# 5_-OPI_MAIN.net
KiCad netlist of a schematic drawn in Altium Designer
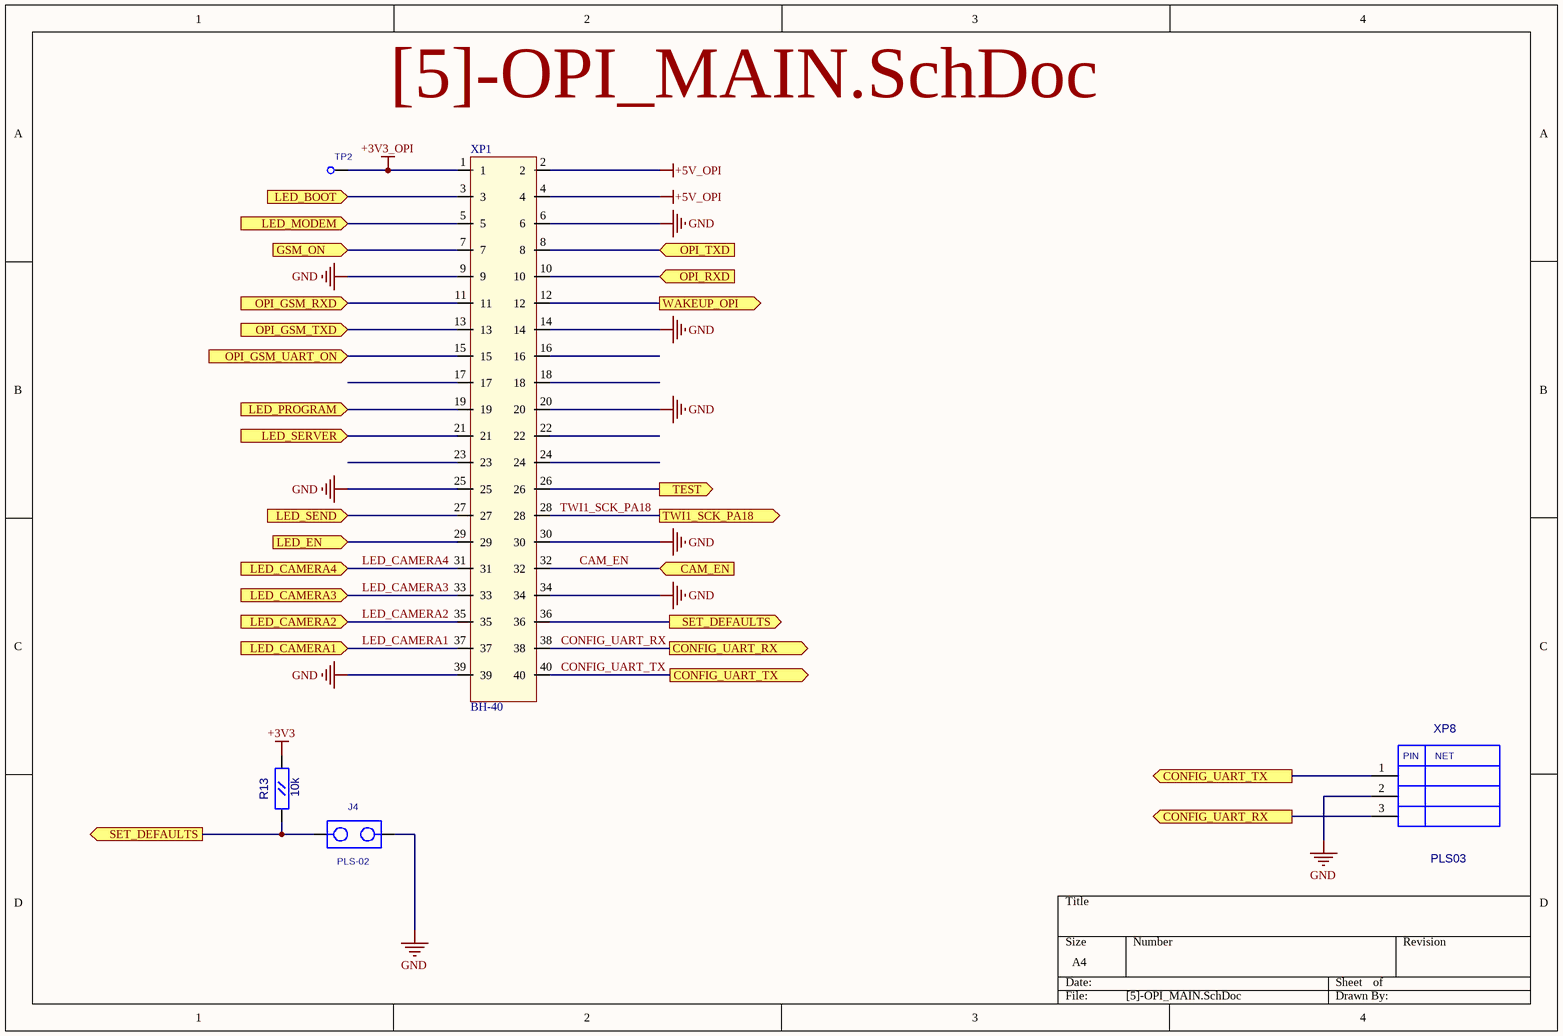
[diagram p0: [5]-OPI_MAIN.SchDoc]

(export (version "E")
  (design (tool "Eeschema 10.0.6"))
  (components
    (comp (ref "J4") (value "PLS-02") (footprint "PLS-02") (libsource (lib "fizik_lib") (part "PLS-02")))
    (comp (ref "R13")
      (value "10k")
      (footprint "RC0603")
      (description "RC0603")
      (libsource (lib "fizik_lib") (part "RC0603"))
    )
    (comp (ref "TP2")
      (value "TESTPOINT1")
      (footprint "TESTPOINT1")
      (libsource (lib "fizik_lib") (part "TESTPOINT1"))
    )
    (comp (ref "XP1")
      (value "BH-40")
      (footprint "BH-40")
      (description "2.54mm connector with key")
      (libsource (lib "fizik_lib") (part "BH-40"))
    )
    (comp (ref "XP8") (value "PLS03") (footprint "PLS-03") (libsource (lib "fizik_lib") (part "PLS03")))
  )
  (nets
    (net (code "1") (name "+3V3") (class "Default")
      (node (ref "R13") (pin "2") (pinfunction "B_2") (pintype "passive"))
    )
    (net (code "2") (name "+3V3_OPI") (class "Default")
      (node (ref "TP2") (pin "1") (pintype "passive"))
      (node (ref "XP1") (pin "1") (pinfunction "1_1") (pintype "passive"))
    )
    (net (code "3") (name "+5V_OPI") (class "Default")
      (node (ref "XP1") (pin "2") (pinfunction "2_2") (pintype "passive"))
      (node (ref "XP1") (pin "4") (pinfunction "4_4") (pintype "passive"))
    )
    (net (code "4") (name "/CAM_EN") (class "Default")
      (node (ref "XP1") (pin "32") (pinfunction "32_32") (pintype "passive"))
    )
    (net (code "5") (name "/CONFIG_UART_RX") (class "Default")
      (node (ref "XP1") (pin "38") (pinfunction "38_38") (pintype "passive"))
      (node (ref "XP8") (pin "3") (pinfunction "3_3") (pintype "passive"))
    )
    (net (code "6") (name "/CONFIG_UART_TX") (class "Default")
      (node (ref "XP1") (pin "40") (pinfunction "40_40") (pintype "passive"))
      (node (ref "XP8") (pin "1") (pinfunction "1_1") (pintype "passive"))
    )
    (net (code "7") (name "/GSM_ON") (class "Default")
      (node (ref "XP1") (pin "7") (pinfunction "7_7") (pintype "passive"))
    )
    (net (code "8") (name "/LED_BOOT") (class "Default")
      (node (ref "XP1") (pin "3") (pinfunction "3_3") (pintype "passive"))
    )
    (net (code "9") (name "/LED_CAMERA1") (class "Default")
      (node (ref "XP1") (pin "37") (pinfunction "37_37") (pintype "passive"))
    )
    (net (code "10") (name "/LED_CAMERA2") (class "Default")
      (node (ref "XP1") (pin "35") (pinfunction "35_35") (pintype "passive"))
    )
    (net (code "11") (name "/LED_CAMERA3") (class "Default")
      (node (ref "XP1") (pin "33") (pinfunction "33_33") (pintype "passive"))
    )
    (net (code "12") (name "/LED_CAMERA4") (class "Default")
      (node (ref "XP1") (pin "31") (pinfunction "31_31") (pintype "passive"))
    )
    (net (code "13") (name "/LED_EN") (class "Default")
      (node (ref "XP1") (pin "29") (pinfunction "29_29") (pintype "passive"))
    )
    (net (code "14") (name "/LED_MODEM") (class "Default")
      (node (ref "XP1") (pin "5") (pinfunction "5_5") (pintype "passive"))
    )
    (net (code "15") (name "/LED_PROGRAM") (class "Default")
      (node (ref "XP1") (pin "19") (pinfunction "19_19") (pintype "passive"))
    )
    (net (code "16") (name "/LED_SEND") (class "Default")
      (node (ref "XP1") (pin "27") (pinfunction "27_27") (pintype "passive"))
    )
    (net (code "17") (name "/LED_SERVER") (class "Default")
      (node (ref "XP1") (pin "21") (pinfunction "21_21") (pintype "passive"))
    )
    (net (code "18") (name "/OPI_GSM_RXD") (class "Default")
      (node (ref "XP1") (pin "11") (pinfunction "11_11") (pintype "passive"))
    )
    (net (code "19") (name "/OPI_GSM_TXD") (class "Default")
      (node (ref "XP1") (pin "13") (pinfunction "13_13") (pintype "passive"))
    )
    (net (code "20") (name "/OPI_GSM_UART_ON") (class "Default")
      (node (ref "XP1") (pin "15") (pinfunction "15_15") (pintype "passive"))
    )
    (net (code "21") (name "/OPI_RXD") (class "Default")
      (node (ref "XP1") (pin "10") (pinfunction "10_10") (pintype "passive"))
    )
    (net (code "22") (name "/OPI_TXD") (class "Default")
      (node (ref "XP1") (pin "8") (pinfunction "8_8") (pintype "passive"))
    )
    (net (code "23") (name "/SET_DEFAULTS") (class "Default")
      (node (ref "J4") (pin "1") (pintype "passive"))
      (node (ref "R13") (pin "1") (pinfunction "A_1") (pintype "passive"))
      (node (ref "XP1") (pin "36") (pinfunction "36_36") (pintype "passive"))
    )
    (net (code "24") (name "/TEST") (class "Default")
      (node (ref "XP1") (pin "26") (pinfunction "26_26") (pintype "passive"))
    )
    (net (code "25") (name "/TWI1_SCK_PA18") (class "Default")
      (node (ref "XP1") (pin "28") (pinfunction "28_28") (pintype "passive"))
    )
    (net (code "26") (name "/WAKEUP_OPI") (class "Default")
      (node (ref "XP1") (pin "12") (pinfunction "12_12") (pintype "passive"))
    )
    (net (code "27") (name "GND") (class "Default")
      (node (ref "J4") (pin "2") (pintype "passive"))
      (node (ref "XP1") (pin "14") (pinfunction "14_14") (pintype "passive"))
      (node (ref "XP1") (pin "20") (pinfunction "20_20") (pintype "passive"))
      (node (ref "XP1") (pin "25") (pinfunction "25_25") (pintype "passive"))
      (node (ref "XP1") (pin "30") (pinfunction "30_30") (pintype "passive"))
      (node (ref "XP1") (pin "34") (pinfunction "34_34") (pintype "passive"))
      (node (ref "XP1") (pin "39") (pinfunction "39_39") (pintype "passive"))
      (node (ref "XP1") (pin "6") (pinfunction "6_6") (pintype "passive"))
      (node (ref "XP1") (pin "9") (pinfunction "9_9") (pintype "passive"))
      (node (ref "XP8") (pin "2") (pinfunction "2_2") (pintype "passive"))
    )
    (net (code "28") (name "unconnected-(XP1-Pad16)") (class "Default")
      (node (ref "XP1") (pin "16") (pinfunction "16_16") (pintype "passive"))
    )
    (net (code "29") (name "unconnected-(XP1-Pad17)") (class "Default")
      (node (ref "XP1") (pin "17") (pinfunction "17_17") (pintype "passive"))
    )
    (net (code "30") (name "unconnected-(XP1-Pad18)") (class "Default")
      (node (ref "XP1") (pin "18") (pinfunction "18_18") (pintype "passive"))
    )
    (net (code "31") (name "unconnected-(XP1-Pad22)") (class "Default")
      (node (ref "XP1") (pin "22") (pinfunction "22_22") (pintype "passive"))
    )
    (net (code "32") (name "unconnected-(XP1-Pad23)") (class "Default")
      (node (ref "XP1") (pin "23") (pinfunction "23_23") (pintype "passive"))
    )
    (net (code "33") (name "unconnected-(XP1-Pad24)") (class "Default")
      (node (ref "XP1") (pin "24") (pinfunction "24_24") (pintype "passive"))
    )
  )
)
